# led_board_RGB-3hole.net
KiCad netlist of a schematic drawn in EAGLE
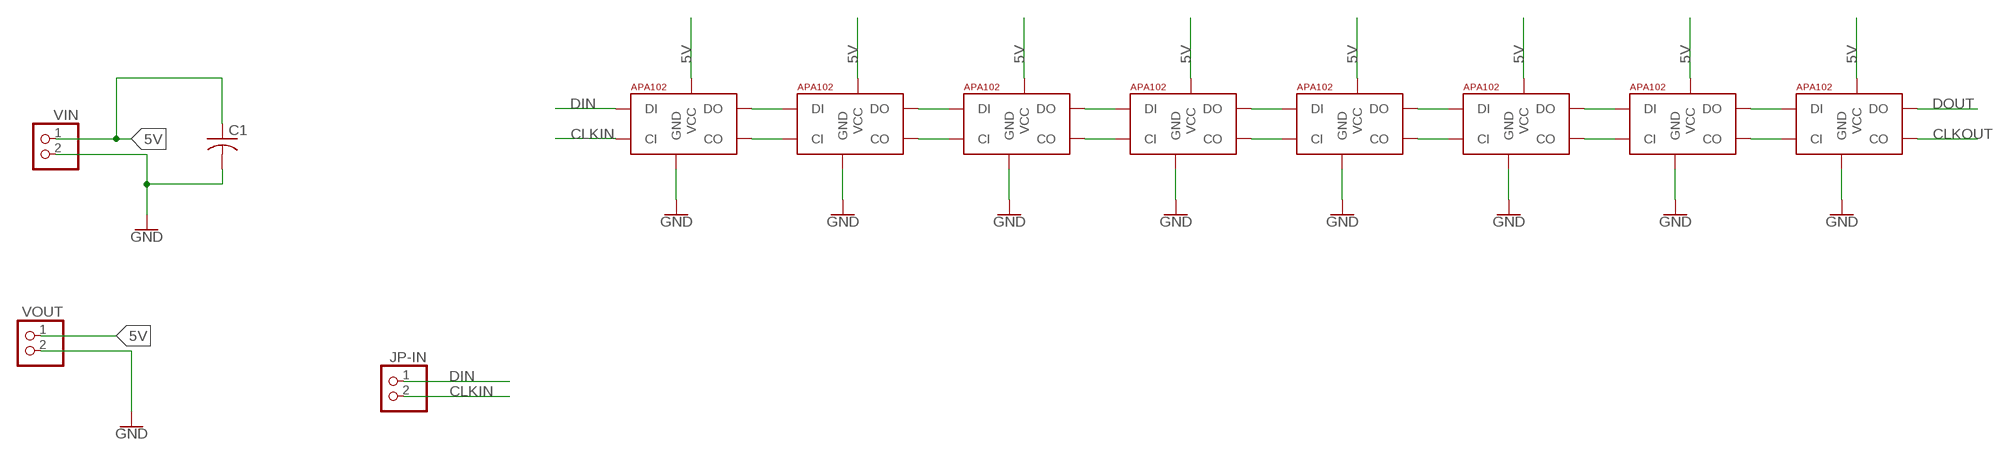
[diagram p0: schematic, sheet 1]

(export (version "E")
  (design (tool "Eeschema 10.0.6"))
  (components
    (comp (ref "C1")
      (value "C-US025-030X050")
      (footprint "eagle-import:C025-030X050")
      (libsource (lib "eagle-import") (part "C-US025-030X050"))
    )
    (comp (ref "ED4")
      (value "APA1025050")
      (footprint "eagle-import:APA102_5050")
      (libsource (lib "eagle-import") (part "APA1025050"))
    )
    (comp (ref "JP-IN")
      (value "PINHD-1X2")
      (footprint "eagle-import:1X02")
      (libsource (lib "eagle-import") (part "PINHD-1X2"))
    )
    (comp (ref "LED0")
      (value "APA1025050")
      (footprint "eagle-import:APA102_5050")
      (libsource (lib "eagle-import") (part "APA1025050"))
    )
    (comp (ref "LED1")
      (value "APA1025050")
      (footprint "eagle-import:APA102_5050")
      (libsource (lib "eagle-import") (part "APA1025050"))
    )
    (comp (ref "LED2")
      (value "APA1025050")
      (footprint "eagle-import:APA102_5050")
      (libsource (lib "eagle-import") (part "APA1025050"))
    )
    (comp (ref "LED3")
      (value "APA1025050")
      (footprint "eagle-import:APA102_5050")
      (libsource (lib "eagle-import") (part "APA1025050"))
    )
    (comp (ref "LED5")
      (value "APA1025050")
      (footprint "eagle-import:APA102_5050")
      (libsource (lib "eagle-import") (part "APA1025050"))
    )
    (comp (ref "LED6")
      (value "APA1025050")
      (footprint "eagle-import:APA102_5050")
      (libsource (lib "eagle-import") (part "APA1025050"))
    )
    (comp (ref "LED7")
      (value "APA1025050")
      (footprint "eagle-import:APA102_5050")
      (libsource (lib "eagle-import") (part "APA1025050"))
    )
    (comp (ref "VIN")
      (value "PINHD-1X2")
      (footprint "eagle-import:1X02")
      (libsource (lib "eagle-import") (part "PINHD-1X2"))
    )
    (comp (ref "VOUT")
      (value "PINHD-1X2")
      (footprint "eagle-import:1X02")
      (libsource (lib "eagle-import") (part "PINHD-1X2"))
    )
  )
  (nets
    (net (code "1") (name "/CLKIN") (class "Default")
      (node (ref "JP-IN") (pin "2") (pinfunction "2_2") (pintype "passive"))
      (node (ref "LED0") (pin "5") (pinfunction "CI_5") (pintype "bidirectional"))
    )
    (net (code "2") (name "/CLKOUT") (class "Default")
      (node (ref "LED7") (pin "2") (pinfunction "CO_2") (pintype "bidirectional"))
    )
    (net (code "3") (name "/DIN") (class "Default")
      (node (ref "JP-IN") (pin "1") (pinfunction "1_1") (pintype "passive"))
      (node (ref "LED0") (pin "4") (pinfunction "DI_4") (pintype "bidirectional"))
    )
    (net (code "4") (name "/DOUT") (class "Default")
      (node (ref "LED7") (pin "3") (pinfunction "DO_3") (pintype "bidirectional"))
    )
    (net (code "5") (name "5V") (class "Default")
      (node (ref "C1") (pin "1") (pinfunction "1_1") (pintype "passive"))
      (node (ref "ED4") (pin "1") (pinfunction "VCC_1") (pintype "bidirectional"))
      (node (ref "LED0") (pin "1") (pinfunction "VCC_1") (pintype "bidirectional"))
      (node (ref "LED1") (pin "1") (pinfunction "VCC_1") (pintype "bidirectional"))
      (node (ref "LED2") (pin "1") (pinfunction "VCC_1") (pintype "bidirectional"))
      (node (ref "LED3") (pin "1") (pinfunction "VCC_1") (pintype "bidirectional"))
      (node (ref "LED5") (pin "1") (pinfunction "VCC_1") (pintype "bidirectional"))
      (node (ref "LED6") (pin "1") (pinfunction "VCC_1") (pintype "bidirectional"))
      (node (ref "LED7") (pin "1") (pinfunction "VCC_1") (pintype "bidirectional"))
      (node (ref "VIN") (pin "1") (pinfunction "1_1") (pintype "passive"))
      (node (ref "VOUT") (pin "1") (pinfunction "1_1") (pintype "passive"))
    )
    (net (code "6") (name "GND") (class "Default")
      (node (ref "C1") (pin "2") (pinfunction "2_2") (pintype "passive"))
      (node (ref "ED4") (pin "6") (pinfunction "GND_6") (pintype "bidirectional"))
      (node (ref "LED0") (pin "6") (pinfunction "GND_6") (pintype "bidirectional"))
      (node (ref "LED1") (pin "6") (pinfunction "GND_6") (pintype "bidirectional"))
      (node (ref "LED2") (pin "6") (pinfunction "GND_6") (pintype "bidirectional"))
      (node (ref "LED3") (pin "6") (pinfunction "GND_6") (pintype "bidirectional"))
      (node (ref "LED5") (pin "6") (pinfunction "GND_6") (pintype "bidirectional"))
      (node (ref "LED6") (pin "6") (pinfunction "GND_6") (pintype "bidirectional"))
      (node (ref "LED7") (pin "6") (pinfunction "GND_6") (pintype "bidirectional"))
      (node (ref "VIN") (pin "2") (pinfunction "2_2") (pintype "passive"))
      (node (ref "VOUT") (pin "2") (pinfunction "2_2") (pintype "passive"))
    )
    (net (code "7") (name "Net-(ED4-CI)") (class "Default")
      (node (ref "ED4") (pin "5") (pinfunction "CI_5") (pintype "bidirectional"))
      (node (ref "LED3") (pin "2") (pinfunction "CO_2") (pintype "bidirectional"))
    )
    (net (code "8") (name "Net-(ED4-CO)") (class "Default")
      (node (ref "ED4") (pin "2") (pinfunction "CO_2") (pintype "bidirectional"))
      (node (ref "LED5") (pin "5") (pinfunction "CI_5") (pintype "bidirectional"))
    )
    (net (code "9") (name "Net-(ED4-DI)") (class "Default")
      (node (ref "ED4") (pin "4") (pinfunction "DI_4") (pintype "bidirectional"))
      (node (ref "LED3") (pin "3") (pinfunction "DO_3") (pintype "bidirectional"))
    )
    (net (code "10") (name "Net-(ED4-DO)") (class "Default")
      (node (ref "ED4") (pin "3") (pinfunction "DO_3") (pintype "bidirectional"))
      (node (ref "LED5") (pin "4") (pinfunction "DI_4") (pintype "bidirectional"))
    )
    (net (code "11") (name "Net-(LED0-CO)") (class "Default")
      (node (ref "LED0") (pin "2") (pinfunction "CO_2") (pintype "bidirectional"))
      (node (ref "LED1") (pin "5") (pinfunction "CI_5") (pintype "bidirectional"))
    )
    (net (code "12") (name "Net-(LED0-DO)") (class "Default")
      (node (ref "LED0") (pin "3") (pinfunction "DO_3") (pintype "bidirectional"))
      (node (ref "LED1") (pin "4") (pinfunction "DI_4") (pintype "bidirectional"))
    )
    (net (code "13") (name "Net-(LED1-CO)") (class "Default")
      (node (ref "LED1") (pin "2") (pinfunction "CO_2") (pintype "bidirectional"))
      (node (ref "LED2") (pin "5") (pinfunction "CI_5") (pintype "bidirectional"))
    )
    (net (code "14") (name "Net-(LED1-DO)") (class "Default")
      (node (ref "LED1") (pin "3") (pinfunction "DO_3") (pintype "bidirectional"))
      (node (ref "LED2") (pin "4") (pinfunction "DI_4") (pintype "bidirectional"))
    )
    (net (code "15") (name "Net-(LED2-CO)") (class "Default")
      (node (ref "LED2") (pin "2") (pinfunction "CO_2") (pintype "bidirectional"))
      (node (ref "LED3") (pin "5") (pinfunction "CI_5") (pintype "bidirectional"))
    )
    (net (code "16") (name "Net-(LED2-DO)") (class "Default")
      (node (ref "LED2") (pin "3") (pinfunction "DO_3") (pintype "bidirectional"))
      (node (ref "LED3") (pin "4") (pinfunction "DI_4") (pintype "bidirectional"))
    )
    (net (code "17") (name "Net-(LED5-CO)") (class "Default")
      (node (ref "LED5") (pin "2") (pinfunction "CO_2") (pintype "bidirectional"))
      (node (ref "LED6") (pin "5") (pinfunction "CI_5") (pintype "bidirectional"))
    )
    (net (code "18") (name "Net-(LED5-DO)") (class "Default")
      (node (ref "LED5") (pin "3") (pinfunction "DO_3") (pintype "bidirectional"))
      (node (ref "LED6") (pin "4") (pinfunction "DI_4") (pintype "bidirectional"))
    )
    (net (code "19") (name "Net-(LED6-CO)") (class "Default")
      (node (ref "LED6") (pin "2") (pinfunction "CO_2") (pintype "bidirectional"))
      (node (ref "LED7") (pin "5") (pinfunction "CI_5") (pintype "bidirectional"))
    )
    (net (code "20") (name "Net-(LED6-DO)") (class "Default")
      (node (ref "LED6") (pin "3") (pinfunction "DO_3") (pintype "bidirectional"))
      (node (ref "LED7") (pin "4") (pinfunction "DI_4") (pintype "bidirectional"))
    )
  )
)
